# Node.net
KiCad netlist of a schematic drawn in Altium Designer
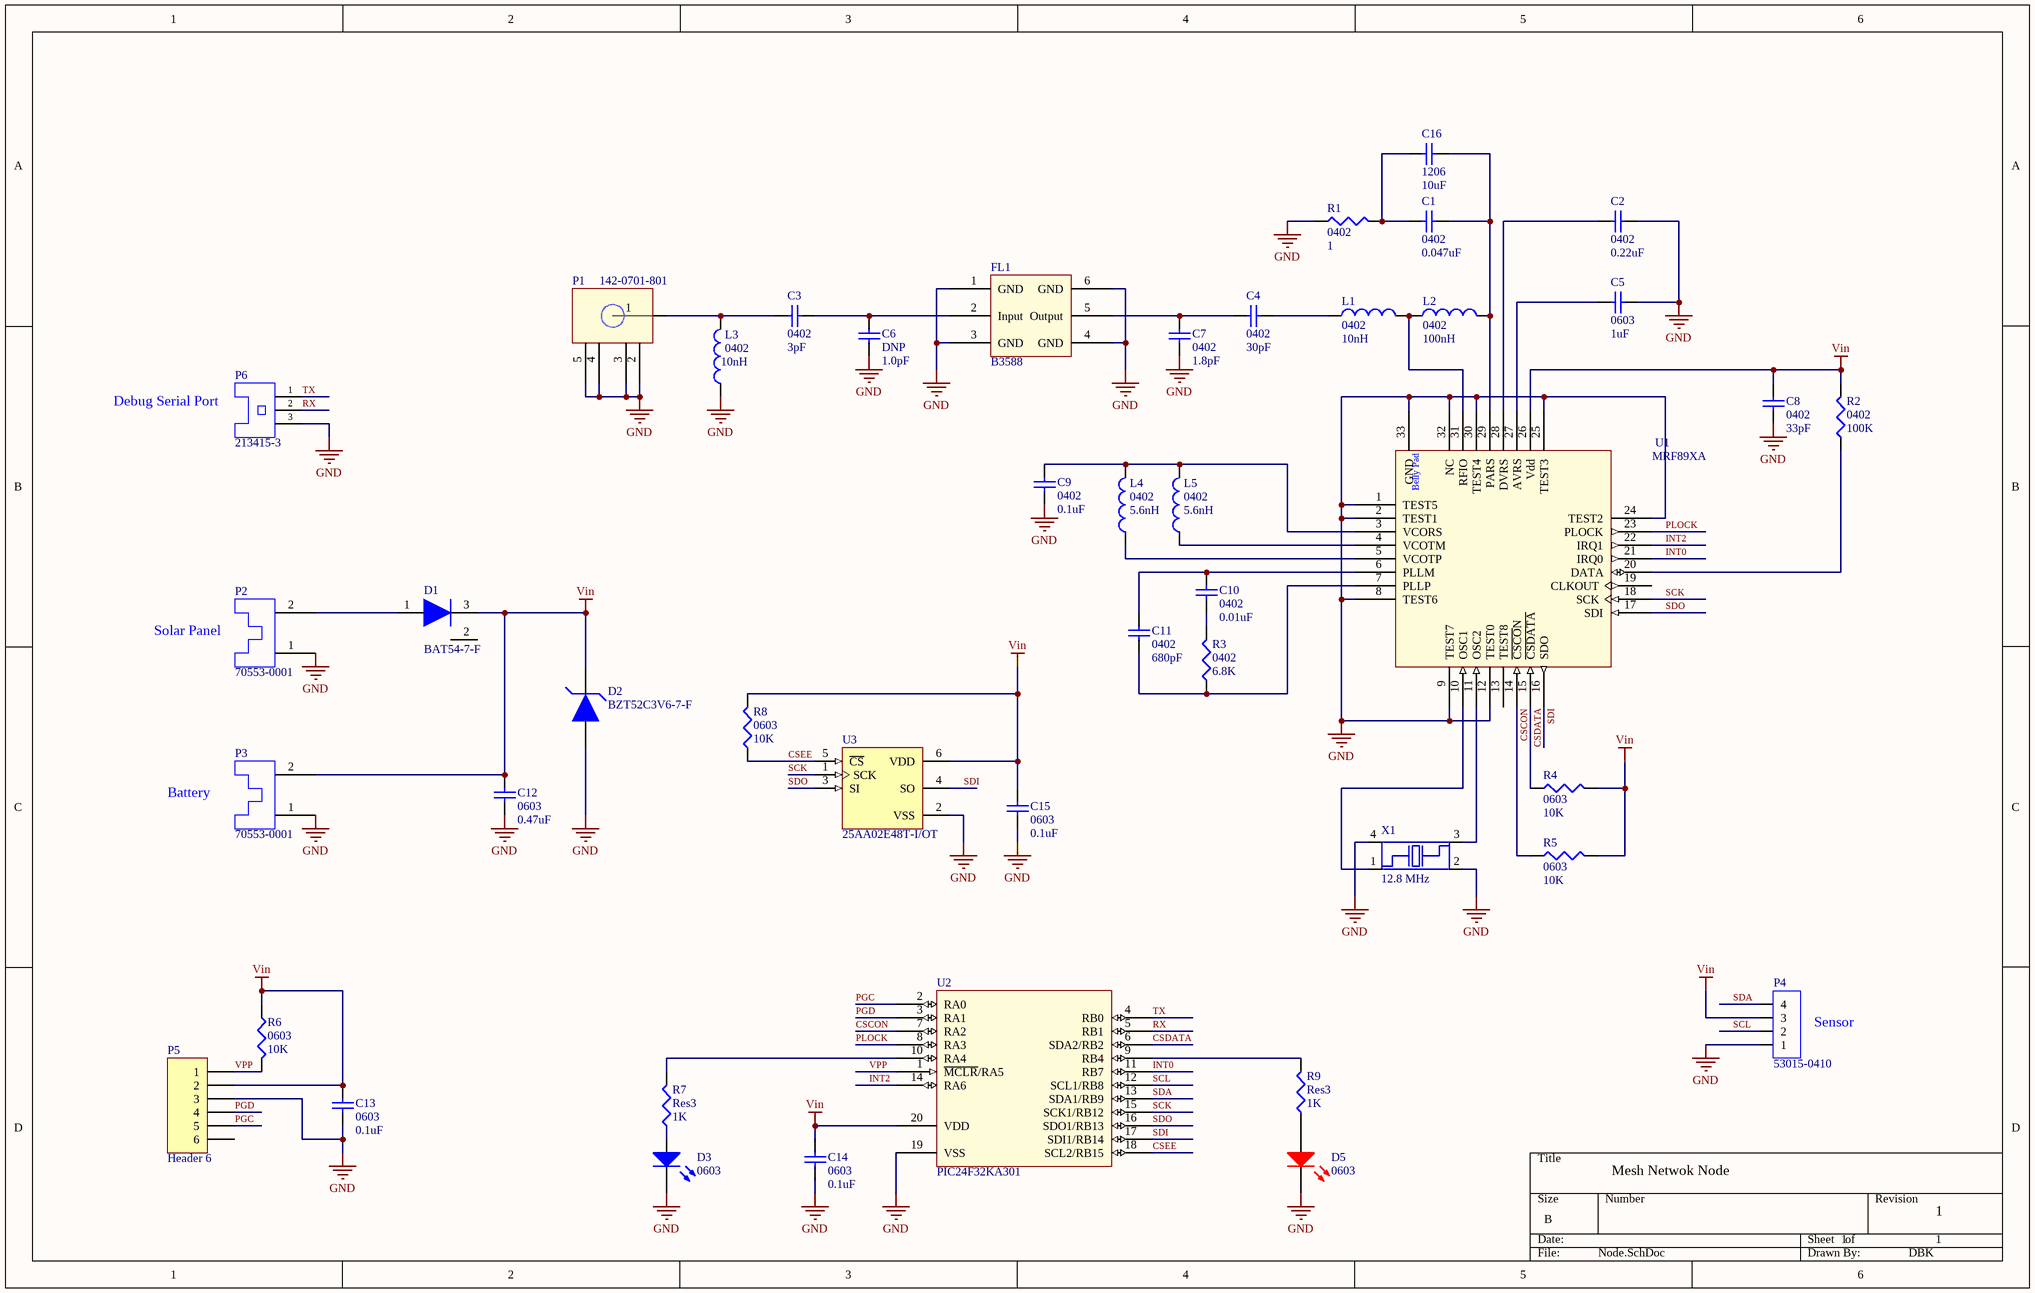
[diagram p0: Node.SchDoc]

(export (version "E")
  (design (tool "Eeschema 10.0.6"))
  (components
    (comp (ref "C1")
      (value "0402")
      (footprint "0402")
      (description "Capacitor (Semiconductor SIM Model)")
      (fields (field (name "ALTIUM_VALUE") "0.047uF") (field (name "PUBLISHER") "Altium Limited"))
      (libsource (lib "Miscellaneous Devices") (part "Cap Semi"))
    )
    (comp (ref "C2")
      (value "0402")
      (footprint "0402")
      (description "Capacitor (Semiconductor SIM Model)")
      (fields (field (name "ALTIUM_VALUE") "0.22uF") (field (name "PUBLISHER") "Altium Limited"))
      (libsource (lib "Miscellaneous Devices") (part "Cap Semi"))
    )
    (comp (ref "C3")
      (value "0402")
      (footprint "0402")
      (description "Capacitor (Semiconductor SIM Model)")
      (fields (field (name "ALTIUM_VALUE") "3pF") (field (name "PUBLISHER") "Altium Limited"))
      (libsource (lib "Miscellaneous Devices") (part "Cap Semi"))
    )
    (comp (ref "C4")
      (value "0402")
      (footprint "0402")
      (description "Capacitor (Semiconductor SIM Model)")
      (fields (field (name "ALTIUM_VALUE") "30pF") (field (name "PUBLISHER") "Altium Limited"))
      (libsource (lib "Miscellaneous Devices") (part "Cap Semi"))
    )
    (comp (ref "C5")
      (value "0603")
      (footprint "0402")
      (description "Capacitor (Semiconductor SIM Model)")
      (fields (field (name "ALTIUM_VALUE") "1uF") (field (name "PUBLISHER") "Altium Limited"))
      (libsource (lib "Miscellaneous Devices") (part "Cap Semi"))
    )
    (comp (ref "C6")
      (value "DNP")
      (footprint "0402")
      (description "Capacitor (Semiconductor SIM Model)")
      (fields (field (name "ALTIUM_VALUE") "1.0pF") (field (name "PUBLISHER") "Altium Limited"))
      (libsource (lib "Miscellaneous Devices") (part "Cap Semi"))
    )
    (comp (ref "C7")
      (value "0402")
      (footprint "0402")
      (description "Capacitor (Semiconductor SIM Model)")
      (fields (field (name "ALTIUM_VALUE") "1.8pF") (field (name "PUBLISHER") "Altium Limited"))
      (libsource (lib "Miscellaneous Devices") (part "Cap Semi"))
    )
    (comp (ref "C8")
      (value "0402")
      (footprint "0402")
      (description "Capacitor (Semiconductor SIM Model)")
      (fields (field (name "ALTIUM_VALUE") "33pF") (field (name "PUBLISHER") "Altium Limited"))
      (libsource (lib "Miscellaneous Devices") (part "Cap Semi"))
    )
    (comp (ref "C9")
      (value "0402")
      (footprint "0402")
      (description "Capacitor (Semiconductor SIM Model)")
      (fields (field (name "ALTIUM_VALUE") "0.1uF") (field (name "PUBLISHER") "Altium Limited"))
      (libsource (lib "Miscellaneous Devices") (part "Cap Semi"))
    )
    (comp (ref "C10")
      (value "0402")
      (footprint "0402")
      (description "Capacitor (Semiconductor SIM Model)")
      (fields (field (name "ALTIUM_VALUE") "0.01uF") (field (name "PUBLISHER") "Altium Limited"))
      (libsource (lib "Miscellaneous Devices") (part "Cap Semi"))
    )
    (comp (ref "C11")
      (value "0402")
      (footprint "0402")
      (description "Capacitor (Semiconductor SIM Model)")
      (fields (field (name "ALTIUM_VALUE") "680pF") (field (name "PUBLISHER") "Altium Limited"))
      (libsource (lib "Miscellaneous Devices") (part "Cap Semi"))
    )
    (comp (ref "C12")
      (value "0603")
      (footprint "1608[0603]")
      (description "Capacitor (Semiconductor SIM Model)")
      (fields (field (name "ALTIUM_VALUE") "0.47uF") (field (name "PUBLISHER") "Altium Limited"))
      (libsource (lib "Miscellaneous Devices") (part "Cap Semi"))
    )
    (comp (ref "C13")
      (value "0603")
      (footprint "1608[0603]")
      (description "Capacitor (Semiconductor SIM Model)")
      (fields (field (name "ALTIUM_VALUE") "0.1uF") (field (name "PUBLISHER") "Altium Limited"))
      (libsource (lib "Miscellaneous Devices") (part "Cap Semi"))
    )
    (comp (ref "C14")
      (value "0603")
      (footprint "1608[0603]")
      (description "Capacitor (Semiconductor SIM Model)")
      (fields (field (name "ALTIUM_VALUE") "0.1uF") (field (name "PUBLISHER") "Altium Limited"))
      (libsource (lib "Miscellaneous Devices") (part "Cap Semi"))
    )
    (comp (ref "C15")
      (value "0603")
      (footprint "1608[0603]")
      (description "Capacitor (Semiconductor SIM Model)")
      (fields (field (name "ALTIUM_VALUE") "0.1uF") (field (name "PUBLISHER") "Altium Limited"))
      (libsource (lib "Miscellaneous Devices") (part "Cap Semi"))
    )
    (comp (ref "C16")
      (value "1206")
      (footprint "1206 CAP")
      (description "Surface Mount Ceramic Capacitor")
      (fields (field (name "ALTIUM_VALUE") "10uF"))
      (libsource (lib "Generic") (part "1206 Capacitor"))
    )
    (comp (ref "D1")
      (value "BAT54-7-F")
      (footprint "SOT90P240X110-3N")
      (description "Schottky Barrier Diode, 200mA")
      (libsource (lib "Node Schematic Library") (part "BAT54-7-F"))
    )
    (comp (ref "D2")
      (value "BZT52C3V6-7-F")
      (footprint "SOD-123")
      (description "Zener Diode, 3.6V, 500 mW")
      (libsource (lib "Node Schematic Library") (part "BZT52C3V6-7-F"))
    )
    (comp (ref "D3")
      (value "0603")
      (footprint "0603 LED")
      (description "Blue LED")
      (fields (field (name "PUBLISHER") "Altium Limited"))
      (libsource (lib "Node Schematic Library") (part "Blue LED"))
    )
    (comp (ref "D5")
      (value "0603")
      (footprint "0603 LED")
      (description "Red LED")
      (fields (field (name "PUBLISHER") "Altium Limited"))
      (libsource (lib "Node Schematic Library") (part "Red LED"))
    )
    (comp (ref "FL1")
      (value "B3588")
      (footprint "B3717")
      (description "915 MHz Saw Filter")
      (libsource (lib "Node Schematic Library") (part "B3588"))
    )
    (comp (ref "L1")
      (value "0402")
      (footprint "0402-A")
      (description "Inductor")
      (fields (field (name "ALTIUM_VALUE") "10nH") (field (name "PUBLISHER") "Altium Limited"))
      (libsource (lib "Miscellaneous Devices") (part "Inductor"))
    )
    (comp (ref "L2")
      (value "0402")
      (footprint "0402-A")
      (description "Inductor")
      (fields (field (name "ALTIUM_VALUE") "100nH") (field (name "PUBLISHER") "Altium Limited"))
      (libsource (lib "Miscellaneous Devices") (part "Inductor"))
    )
    (comp (ref "L3")
      (value "0402")
      (footprint "0402-A")
      (description "Inductor")
      (fields (field (name "ALTIUM_VALUE") "10nH") (field (name "PUBLISHER") "Altium Limited"))
      (libsource (lib "Miscellaneous Devices") (part "Inductor"))
    )
    (comp (ref "L4")
      (value "0402")
      (footprint "0402-A")
      (description "Inductor")
      (fields (field (name "ALTIUM_VALUE") "5.6nH") (field (name "PUBLISHER") "Altium Limited"))
      (libsource (lib "Miscellaneous Devices") (part "Inductor"))
    )
    (comp (ref "L5")
      (value "0402")
      (footprint "0402-A")
      (description "Inductor")
      (fields (field (name "ALTIUM_VALUE") "5.6nH") (field (name "PUBLISHER") "Altium Limited"))
      (libsource (lib "Miscellaneous Devices") (part "Inductor"))
    )
    (comp (ref "P1")
      (value "142-0701-801")
      (footprint "142-0701-801")
      (description "SMA 50 ohm Female Socket, End Launch")
      (libsource (lib "Node Schematic Library") (part "142-0701-801"))
    )
    (comp (ref "P2")
      (value "70553-0001")
      (footprint "070553-0001")
      (description "Header, Shrouded, 2 Pin, RA")
      (libsource (lib "Node Schematic Library") (part "70553-0001"))
    )
    (comp (ref "P3")
      (value "70553-0001")
      (footprint "070553-0001")
      (description "Header, Shrouded, 2 Pin, RA")
      (libsource (lib "Node Schematic Library") (part "70553-0001"))
    )
    (comp (ref "P4")
      (value "53015-0410")
      (footprint "53015-0410")
      (description "4 Position, 2.00 mm Header, RA")
      (libsource (lib "Node Schematic Library") (part "53015-0410"))
    )
    (comp (ref "P5")
      (value "Header 6")
      (footprint "HDR1X6")
      (description "Header, 6-Pin")
      (fields (field (name "PUBLISHER") "Altium Limited"))
      (libsource (lib "Miscellaneous Connectors") (part "Header 6"))
    )
    (comp (ref "P6")
      (value "213415-3")
      (footprint "2132415-3")
      (description "3 Position Vertical Header, 2.5 mm")
      (libsource (lib "Node Schematic Library") (part "213415-3"))
    )
    (comp (ref "R1")
      (value "0402")
      (description "Resistor")
      (fields (field (name "ALTIUM_VALUE") "1") (field (name "PUBLISHER") "Altium Limited"))
      (libsource (lib "Miscellaneous Devices") (part "Res3"))
    )
    (comp (ref "R2")
      (value "0402")
      (footprint "0402")
      (description "Resistor")
      (fields (field (name "ALTIUM_VALUE") "100K") (field (name "PUBLISHER") "Altium Limited"))
      (libsource (lib "Miscellaneous Devices") (part "Res3"))
    )
    (comp (ref "R3")
      (value "0402")
      (footprint "0402")
      (description "Resistor")
      (fields (field (name "ALTIUM_VALUE") "6.8K") (field (name "PUBLISHER") "Altium Limited"))
      (libsource (lib "Miscellaneous Devices") (part "Res3"))
    )
    (comp (ref "R4")
      (value "0603")
      (footprint "J1-0603")
      (description "Resistor")
      (fields (field (name "ALTIUM_VALUE") "10K") (field (name "PUBLISHER") "Altium Limited"))
      (libsource (lib "Miscellaneous Devices") (part "Res3"))
    )
    (comp (ref "R5")
      (value "0603")
      (footprint "J1-0603")
      (description "Resistor")
      (fields (field (name "ALTIUM_VALUE") "10K") (field (name "PUBLISHER") "Altium Limited"))
      (libsource (lib "Miscellaneous Devices") (part "Res3"))
    )
    (comp (ref "R6")
      (value "0603")
      (footprint "J1-0603")
      (description "Resistor")
      (fields (field (name "ALTIUM_VALUE") "10K") (field (name "PUBLISHER") "Altium Limited"))
      (libsource (lib "Miscellaneous Devices") (part "Res3"))
    )
    (comp (ref "R7")
      (value "Res3")
      (footprint "J1-0603")
      (description "Resistor")
      (fields (field (name "ALTIUM_VALUE") "1K") (field (name "PUBLISHER") "Altium Limited"))
      (libsource (lib "Miscellaneous Devices") (part "Res3"))
    )
    (comp (ref "R8")
      (value "0603")
      (footprint "J1-0603")
      (description "Resistor")
      (fields (field (name "ALTIUM_VALUE") "10K") (field (name "PUBLISHER") "Altium Limited"))
      (libsource (lib "Miscellaneous Devices") (part "Res3"))
    )
    (comp (ref "R9")
      (value "Res3")
      (footprint "J1-0603")
      (description "Resistor")
      (fields (field (name "ALTIUM_VALUE") "1K") (field (name "PUBLISHER") "Altium Limited"))
      (libsource (lib "Miscellaneous Devices") (part "Res3"))
    )
    (comp (ref "U1")
      (value "MRF89XA")
      (footprint "QFN50P500X500X75-32N")
      (description "ISM Sub-GHz Transceiver")
      (libsource (lib "Node Schematic Library") (part "MRF89XA"))
    )
    (comp (ref "U2")
      (value "PIC24F32KA301")
      (footprint "SOP127P600-8N")
      (description "PIC Microcontroller, 32K Flash, 20 pin")
      (libsource (lib "Node Schematic Library") (part "PIC24F32KA301"))
    )
    (comp (ref "U3")
      (value "25AA02E48T-I/OT")
      (footprint "SOT-23-OT6_N")
      (fields (field (name "MANUFACTURER") "Microchip"))
      (libsource (lib "Microchip SPI Serial EEPROM") (part "25AA02E48T-I/OT"))
    )
    (comp (ref "X1")
      (value "12.8 MHz")
      (footprint "ABM3B")
      (description "Abracon 12.8 MHz, 10ppm")
      (libsource (lib "Node Schematic Library") (part "ABM3B-155-12.800MHz-T"))
    )
  )
  (nets
    (net (code "1") (name "/CSCON") (class "Default")
      (node (ref "R5") (pin "1") (pinfunction "1_1") (pintype "passive"))
      (node (ref "U1") (pin "14") (pinfunction "~{CSCO}N_14") (pintype "input"))
      (node (ref "U2") (pin "7") (pinfunction "RA2_7") (pintype "bidirectional"))
    )
    (net (code "2") (name "/CSDATA") (class "Default")
      (node (ref "R4") (pin "1") (pinfunction "1_1") (pintype "passive"))
      (node (ref "U1") (pin "15") (pinfunction "~{CSDATA}_15") (pintype "input"))
      (node (ref "U2") (pin "6") (pinfunction "SDA2/RB2_6") (pintype "bidirectional"))
    )
    (net (code "3") (name "/CSEE") (class "Default")
      (node (ref "R8") (pin "1") (pinfunction "1_1") (pintype "passive"))
      (node (ref "U2") (pin "18") (pinfunction "SCL2/RB15_18") (pintype "bidirectional"))
      (node (ref "U3") (pin "5") (pinfunction "~{CS}_5") (pintype "input"))
    )
    (net (code "4") (name "/INT0") (class "Default")
      (node (ref "U1") (pin "21") (pinfunction "IRQ0_21") (pintype "output"))
      (node (ref "U2") (pin "11") (pinfunction "RB7_11") (pintype "bidirectional"))
    )
    (net (code "5") (name "/INT2") (class "Default")
      (node (ref "U1") (pin "22") (pinfunction "IRQ1_22") (pintype "output"))
      (node (ref "U2") (pin "14") (pinfunction "RA6_14") (pintype "bidirectional"))
    )
    (net (code "6") (name "/PGC") (class "Default")
      (node (ref "P5") (pin "5") (pinfunction "5_5") (pintype "passive"))
      (node (ref "U2") (pin "2") (pinfunction "RA0_2") (pintype "bidirectional"))
    )
    (net (code "7") (name "/PGD") (class "Default")
      (node (ref "P5") (pin "4") (pinfunction "4_4") (pintype "passive"))
      (node (ref "U2") (pin "3") (pinfunction "RA1_3") (pintype "bidirectional"))
    )
    (net (code "8") (name "/PLOCK") (class "Default")
      (node (ref "U1") (pin "23") (pinfunction "PLOCK_23") (pintype "output"))
      (node (ref "U2") (pin "8") (pinfunction "RA3_8") (pintype "bidirectional"))
    )
    (net (code "9") (name "/RX") (class "Default")
      (node (ref "P6") (pin "2") (pinfunction "2_2") (pintype "passive"))
      (node (ref "U2") (pin "5") (pinfunction "RB1_5") (pintype "bidirectional"))
    )
    (net (code "10") (name "/SCK") (class "Default")
      (node (ref "U1") (pin "18") (pinfunction "SCK_18") (pintype "input"))
      (node (ref "U2") (pin "15") (pinfunction "SCK1/RB12_15") (pintype "bidirectional"))
      (node (ref "U3") (pin "1") (pinfunction "SCK_1") (pintype "input"))
    )
    (net (code "11") (name "/SCL") (class "Default")
      (node (ref "P4") (pin "2") (pinfunction "2_2") (pintype "passive"))
      (node (ref "U2") (pin "12") (pinfunction "SCL1/RB8_12") (pintype "bidirectional"))
    )
    (net (code "12") (name "/SDA") (class "Default")
      (node (ref "P4") (pin "4") (pinfunction "4_4") (pintype "passive"))
      (node (ref "U2") (pin "13") (pinfunction "SDA1/RB9_13") (pintype "bidirectional"))
    )
    (net (code "13") (name "/SDI") (class "Default")
      (node (ref "U1") (pin "16") (pinfunction "SDO_16") (pintype "output"))
      (node (ref "U2") (pin "17") (pinfunction "SDI1/RB14_17") (pintype "bidirectional"))
      (node (ref "U3") (pin "4") (pinfunction "SO_4") (pintype "tri_state"))
    )
    (net (code "14") (name "/SDO") (class "Default")
      (node (ref "U1") (pin "17") (pinfunction "SDI_17") (pintype "input"))
      (node (ref "U2") (pin "16") (pinfunction "SDO1/RB13_16") (pintype "bidirectional"))
      (node (ref "U3") (pin "3") (pinfunction "SI_3") (pintype "input"))
    )
    (net (code "15") (name "/TX") (class "Default")
      (node (ref "P6") (pin "1") (pinfunction "1_1") (pintype "passive"))
      (node (ref "U2") (pin "4") (pinfunction "RB0_4") (pintype "bidirectional"))
    )
    (net (code "16") (name "/VPP") (class "Default")
      (node (ref "P5") (pin "1") (pinfunction "1_1") (pintype "passive"))
      (node (ref "R6") (pin "2") (pinfunction "2_2") (pintype "passive"))
      (node (ref "U2") (pin "1") (pinfunction "~{MCLR}/RA5_1") (pintype "input"))
    )
    (net (code "17") (name "GND") (class "Default")
      (node (ref "C12") (pin "1") (pinfunction "1_1") (pintype "passive"))
      (node (ref "C13") (pin "1") (pinfunction "1_1") (pintype "passive"))
      (node (ref "C14") (pin "1") (pinfunction "1_1") (pintype "passive"))
      (node (ref "C15") (pin "1") (pinfunction "1_1") (pintype "passive"))
      (node (ref "C2") (pin "2") (pinfunction "2_2") (pintype "passive"))
      (node (ref "C5") (pin "1") (pinfunction "1_1") (pintype "passive"))
      (node (ref "C6") (pin "1") (pinfunction "1_1") (pintype "passive"))
      (node (ref "C7") (pin "1") (pinfunction "1_1") (pintype "passive"))
      (node (ref "C8") (pin "2") (pinfunction "2_2") (pintype "passive"))
      (node (ref "C9") (pin "1") (pinfunction "1_1") (pintype "passive"))
      (node (ref "D2") (pin "1") (pinfunction "1_1") (pintype "passive"))
      (node (ref "D3") (pin "1") (pinfunction "K_1") (pintype "passive"))
      (node (ref "D5") (pin "1") (pinfunction "K_1") (pintype "passive"))
      (node (ref "FL1") (pin "1") (pinfunction "GND_1") (pintype "passive"))
      (node (ref "FL1") (pin "3") (pinfunction "GND_3") (pintype "passive"))
      (node (ref "FL1") (pin "4") (pinfunction "GND_4") (pintype "passive"))
      (node (ref "FL1") (pin "6") (pinfunction "GND_6") (pintype "passive"))
      (node (ref "L3") (pin "1") (pinfunction "1_1") (pintype "passive"))
      (node (ref "P1") (pin "2") (pinfunction "2_2") (pintype "passive"))
      (node (ref "P1") (pin "3") (pinfunction "3_3") (pintype "passive"))
      (node (ref "P1") (pin "4") (pinfunction "4_4") (pintype "passive"))
      (node (ref "P1") (pin "5") (pinfunction "5_5") (pintype "passive"))
      (node (ref "P2") (pin "1") (pinfunction "1_1") (pintype "passive"))
      (node (ref "P3") (pin "1") (pinfunction "1_1") (pintype "passive"))
      (node (ref "P4") (pin "1") (pinfunction "1_1") (pintype "passive"))
      (node (ref "P5") (pin "3") (pinfunction "3_3") (pintype "passive"))
      (node (ref "P6") (pin "3") (pinfunction "3_3") (pintype "passive"))
      (node (ref "R1") (pin "1") (pinfunction "1_1") (pintype "passive"))
      (node (ref "U1") (pin "1") (pinfunction "TEST5_1") (pintype "passive"))
      (node (ref "U1") (pin "12") (pinfunction "TEST0_12") (pintype "passive"))
      (node (ref "U1") (pin "2") (pinfunction "TEST1_2") (pintype "passive"))
      (node (ref "U1") (pin "24") (pinfunction "TEST2_24") (pintype "passive"))
      (node (ref "U1") (pin "25") (pinfunction "TEST3_25") (pintype "passive"))
      (node (ref "U1") (pin "30") (pinfunction "TEST4_30") (pintype "passive"))
      (node (ref "U1") (pin "32") (pinfunction "NC_32") (pintype "passive"))
      (node (ref "U1") (pin "33") (pinfunction "GND_33") (pintype "passive"))
      (node (ref "U1") (pin "8") (pinfunction "TEST6_8") (pintype "passive"))
      (node (ref "U1") (pin "9") (pinfunction "TEST7_9") (pintype "passive"))
      (node (ref "U2") (pin "19") (pinfunction "VSS_19") (pintype "passive"))
      (node (ref "U3") (pin "2") (pinfunction "VSS_2") (pintype "power_in"))
      (node (ref "X1") (pin "2") (pintype "passive"))
      (node (ref "X1") (pin "4") (pintype "passive"))
    )
    (net (code "18") (name "Net-(C1-Pad1)") (class "Default")
      (node (ref "C1") (pin "1") (pinfunction "1_1") (pintype "passive"))
      (node (ref "C16") (pin "1") (pinfunction "1_1") (pintype "passive"))
      (node (ref "R1") (pin "2") (pinfunction "2_2") (pintype "passive"))
    )
    (net (code "19") (name "Net-(C4-Pad2)") (class "Default")
      (node (ref "C4") (pin "2") (pinfunction "2_2") (pintype "passive"))
      (node (ref "L1") (pin "1") (pinfunction "1_1") (pintype "passive"))
    )
    (net (code "20") (name "Net-(C10-Pad2)") (class "Default")
      (node (ref "C10") (pin "2") (pinfunction "2_2") (pintype "passive"))
      (node (ref "R3") (pin "2") (pinfunction "2_2") (pintype "passive"))
    )
    (net (code "21") (name "Net-(D1-Pad1)") (class "Default")
      (node (ref "D1") (pin "1") (pinfunction "1_1") (pintype "passive"))
      (node (ref "P2") (pin "2") (pinfunction "2_2") (pintype "passive"))
    )
    (net (code "22") (name "Net-(D3-A)") (class "Default")
      (node (ref "D3") (pin "2") (pinfunction "A_2") (pintype "passive"))
      (node (ref "R7") (pin "1") (pinfunction "1_1") (pintype "passive"))
    )
    (net (code "23") (name "Net-(D5-A)") (class "Default")
      (node (ref "D5") (pin "2") (pinfunction "A_2") (pintype "passive"))
      (node (ref "R9") (pin "1") (pinfunction "1_1") (pintype "passive"))
    )
    (net (code "24") (name "Net-(FL1-Input)") (class "Default")
      (node (ref "C3") (pin "2") (pinfunction "2_2") (pintype "passive"))
      (node (ref "C6") (pin "2") (pinfunction "2_2") (pintype "passive"))
      (node (ref "FL1") (pin "2") (pinfunction "Input_2") (pintype "passive"))
    )
    (net (code "25") (name "Net-(FL1-Output)") (class "Default")
      (node (ref "C4") (pin "1") (pinfunction "1_1") (pintype "passive"))
      (node (ref "C7") (pin "2") (pinfunction "2_2") (pintype "passive"))
      (node (ref "FL1") (pin "5") (pinfunction "Output_5") (pintype "passive"))
    )
    (net (code "26") (name "Net-(P1-Pin)") (class "Default")
      (node (ref "C3") (pin "1") (pinfunction "1_1") (pintype "passive"))
      (node (ref "L3") (pin "2") (pinfunction "2_2") (pintype "passive"))
      (node (ref "P1") (pin "1") (pinfunction "Pin_1") (pintype "passive"))
    )
    (net (code "27") (name "Net-(U1-AVRS)") (class "Default")
      (node (ref "C5") (pin "2") (pinfunction "2_2") (pintype "passive"))
      (node (ref "U1") (pin "27") (pinfunction "AVRS_27") (pintype "passive"))
    )
    (net (code "28") (name "Net-(U1-DATA)") (class "Default")
      (node (ref "R2") (pin "1") (pinfunction "1_1") (pintype "passive"))
      (node (ref "U1") (pin "20") (pinfunction "DATA_20") (pintype "bidirectional"))
    )
    (net (code "29") (name "Net-(U1-DVRS)") (class "Default")
      (node (ref "C2") (pin "1") (pinfunction "1_1") (pintype "passive"))
      (node (ref "U1") (pin "28") (pinfunction "DVRS_28") (pintype "passive"))
    )
    (net (code "30") (name "Net-(U1-OSC1)") (class "Default")
      (node (ref "U1") (pin "10") (pinfunction "OSC1_10") (pintype "input"))
      (node (ref "X1") (pin "1") (pintype "passive"))
    )
    (net (code "31") (name "Net-(U1-OSC2)") (class "Default")
      (node (ref "U1") (pin "11") (pinfunction "OSC2_11") (pintype "input"))
      (node (ref "X1") (pin "3") (pintype "passive"))
    )
    (net (code "32") (name "Net-(U1-PARS)") (class "Default")
      (node (ref "C1") (pin "2") (pinfunction "2_2") (pintype "passive"))
      (node (ref "C16") (pin "2") (pinfunction "2_2") (pintype "passive"))
      (node (ref "L2") (pin "2") (pinfunction "2_2") (pintype "passive"))
      (node (ref "U1") (pin "29") (pinfunction "PARS_29") (pintype "passive"))
    )
    (net (code "33") (name "Net-(U1-PLLM)") (class "Default")
      (node (ref "C10") (pin "1") (pinfunction "1_1") (pintype "passive"))
      (node (ref "C11") (pin "1") (pinfunction "1_1") (pintype "passive"))
      (node (ref "U1") (pin "6") (pinfunction "PLLM_6") (pintype "passive"))
    )
    (net (code "34") (name "Net-(U1-PLLP)") (class "Default")
      (node (ref "C11") (pin "2") (pinfunction "2_2") (pintype "passive"))
      (node (ref "R3") (pin "1") (pinfunction "1_1") (pintype "passive"))
      (node (ref "U1") (pin "7") (pinfunction "PLLP_7") (pintype "passive"))
    )
    (net (code "35") (name "Net-(U1-RFIO)") (class "Default")
      (node (ref "L1") (pin "2") (pinfunction "2_2") (pintype "passive"))
      (node (ref "L2") (pin "1") (pinfunction "1_1") (pintype "passive"))
      (node (ref "U1") (pin "31") (pinfunction "RFIO_31") (pintype "passive"))
    )
    (net (code "36") (name "Net-(U1-VCORS)") (class "Default")
      (node (ref "C9") (pin "2") (pinfunction "2_2") (pintype "passive"))
      (node (ref "L4") (pin "2") (pinfunction "2_2") (pintype "passive"))
      (node (ref "L5") (pin "2") (pinfunction "2_2") (pintype "passive"))
      (node (ref "U1") (pin "3") (pinfunction "VCORS_3") (pintype "passive"))
    )
    (net (code "37") (name "Net-(U1-VCOTM)") (class "Default")
      (node (ref "L5") (pin "1") (pinfunction "1_1") (pintype "passive"))
      (node (ref "U1") (pin "4") (pinfunction "VCOTM_4") (pintype "passive"))
    )
    (net (code "38") (name "Net-(U1-VCOTP)") (class "Default")
      (node (ref "L4") (pin "1") (pinfunction "1_1") (pintype "passive"))
      (node (ref "U1") (pin "5") (pinfunction "VCOTP_5") (pintype "passive"))
    )
    (net (code "39") (name "Net-(U2-RA4)") (class "Default")
      (node (ref "R7") (pin "2") (pinfunction "2_2") (pintype "passive"))
      (node (ref "U2") (pin "10") (pinfunction "RA4_10") (pintype "bidirectional"))
    )
    (net (code "40") (name "Net-(U2-RB4)") (class "Default")
      (node (ref "R9") (pin "2") (pinfunction "2_2") (pintype "passive"))
      (node (ref "U2") (pin "9") (pinfunction "RB4_9") (pintype "bidirectional"))
    )
    (net (code "41") (name "Vin") (class "Default")
      (node (ref "C12") (pin "2") (pinfunction "2_2") (pintype "passive"))
      (node (ref "C13") (pin "2") (pinfunction "2_2") (pintype "passive"))
      (node (ref "C14") (pin "2") (pinfunction "2_2") (pintype "passive"))
      (node (ref "C15") (pin "2") (pinfunction "2_2") (pintype "passive"))
      (node (ref "C8") (pin "1") (pinfunction "1_1") (pintype "passive"))
      (node (ref "D1") (pin "3") (pinfunction "3_3") (pintype "passive"))
      (node (ref "D2") (pin "2") (pinfunction "2_2") (pintype "passive"))
      (node (ref "P3") (pin "2") (pinfunction "2_2") (pintype "passive"))
      (node (ref "P4") (pin "3") (pinfunction "3_3") (pintype "passive"))
      (node (ref "P5") (pin "2") (pinfunction "2_2") (pintype "passive"))
      (node (ref "R2") (pin "2") (pinfunction "2_2") (pintype "passive"))
      (node (ref "R4") (pin "2") (pinfunction "2_2") (pintype "passive"))
      (node (ref "R5") (pin "2") (pinfunction "2_2") (pintype "passive"))
      (node (ref "R6") (pin "1") (pinfunction "1_1") (pintype "passive"))
      (node (ref "R8") (pin "2") (pinfunction "2_2") (pintype "passive"))
      (node (ref "U1") (pin "26") (pinfunction "Vdd_26") (pintype "passive"))
      (node (ref "U2") (pin "20") (pinfunction "VDD_20") (pintype "power_in"))
      (node (ref "U3") (pin "6") (pinfunction "VDD_6") (pintype "power_in"))
    )
    (net (code "42") (name "unconnected-(D1-Pad2)") (class "Default")
      (node (ref "D1") (pin "2") (pinfunction "2_2") (pintype "passive"))
    )
    (net (code "43") (name "unconnected-(P5-Pad6)") (class "Default")
      (node (ref "P5") (pin "6") (pinfunction "6_6") (pintype "passive"))
    )
    (net (code "44") (name "unconnected-(U1-CLKOUT-Pad19)") (class "Default")
      (node (ref "U1") (pin "19") (pinfunction "CLKOUT_19") (pintype "output"))
    )
    (net (code "45") (name "unconnected-(U1-TEST8-Pad13)") (class "Default")
      (node (ref "U1") (pin "13") (pinfunction "TEST8_13") (pintype "passive"))
    )
  )
)
